# ProProject_PetCareSTM32_MiniSTM32_2024-0.net
KiCad netlist of a schematic drawn in EasyEDA Pro
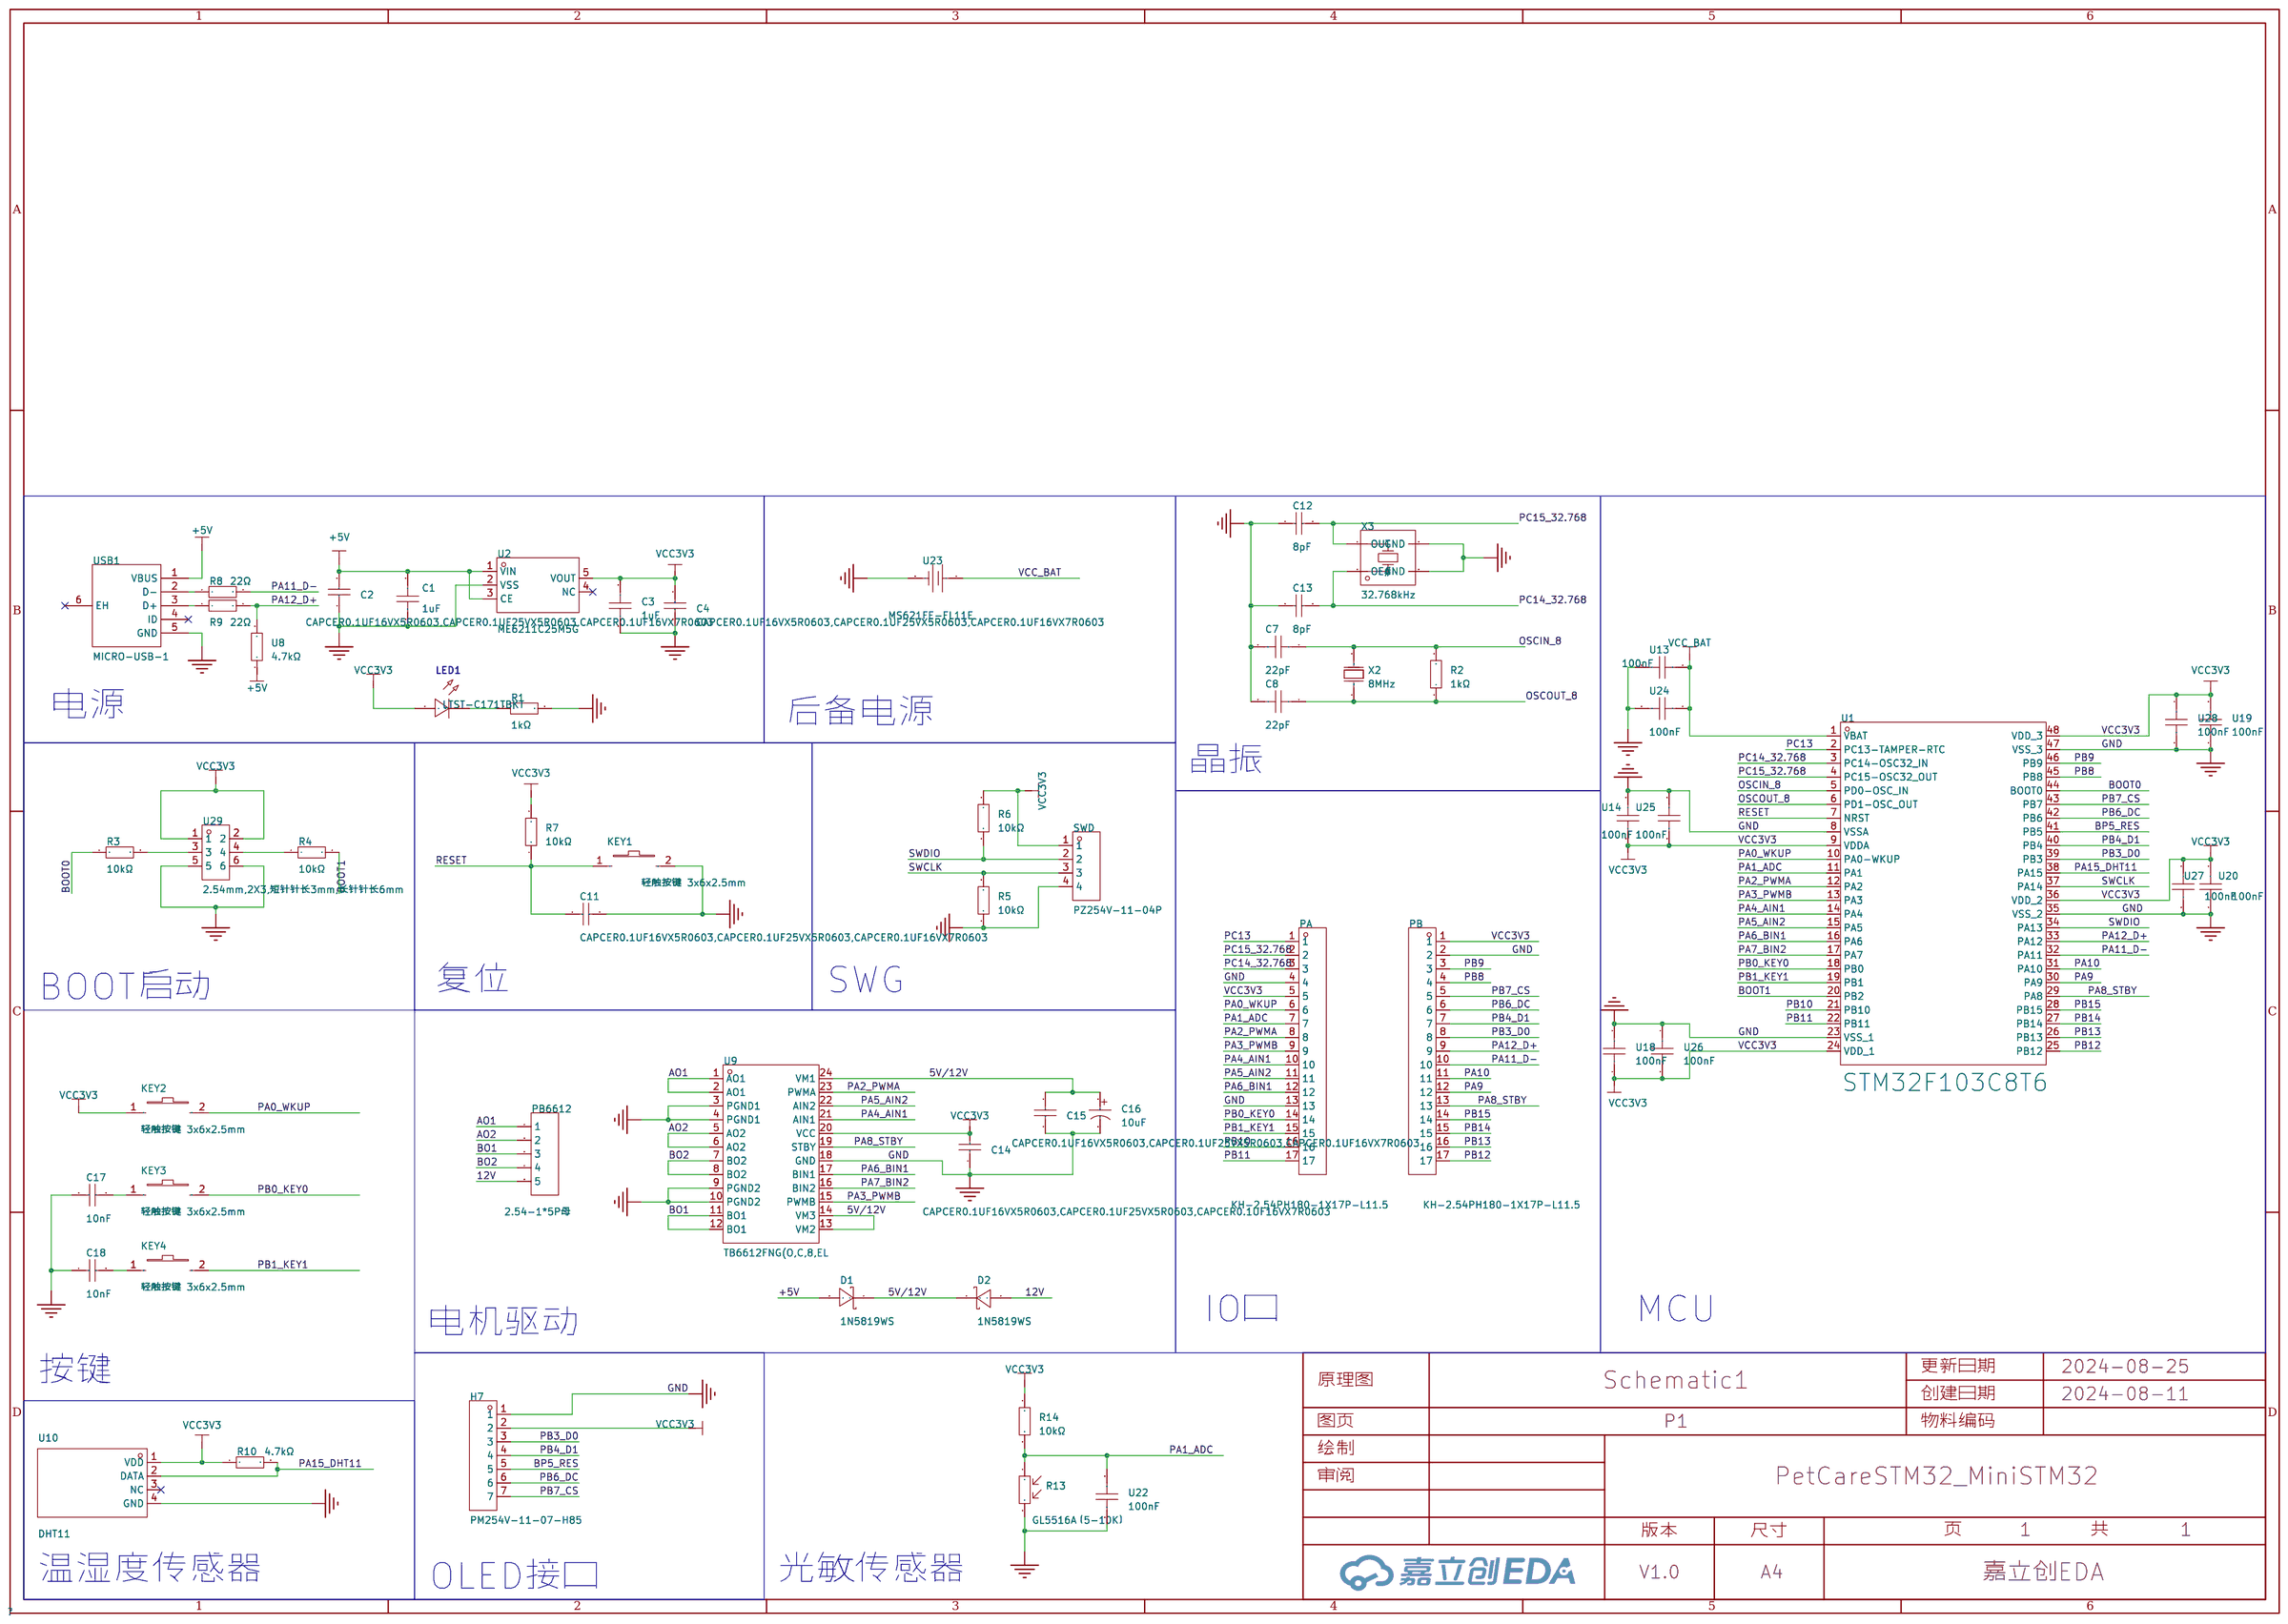
[diagram p0: schematic sheet]

(export (version "E")
  (design (tool "Eeschema 10.0.6"))
  (components
    (comp (ref "C1")
      (value "1uF")
      (footprint "easyedapro:C0603")
      (description "容值:1uF;精度:±10%;额定电压:50V;材质(温度系数):X5R;")
      (fields
        (field (name "Manufacturer Part") "CL10A105KB8NNNC")
        (field (name "Manufacturer") "SAMSUNG(三星)")
      )
      (libsource (lib "easyedapro") (part "CL10A105KB8NNNC"))
    )
    (comp (ref "C2")
      (value "CAPCER0.1UF16VX5R0603,CAPCER0.1UF25VX5R0603,CAPCER0.1UF16VX7R0603")
      (footprint "easyedapro:C0603")
      (libsource (lib "easyedapro") (part "CAPCER0.1UF16VX5R0603,CAPCER0.1UF25VX5R0603,CAPCER0.1UF16VX7R0603"))
    )
    (comp (ref "C3")
      (value "1uF")
      (footprint "easyedapro:C0603")
      (description "容值:1uF;精度:±10%;额定电压:50V;材质(温度系数):X5R;")
      (fields
        (field (name "Manufacturer Part") "CL10A105KB8NNNC")
        (field (name "Manufacturer") "SAMSUNG(三星)")
      )
      (libsource (lib "easyedapro") (part "CL10A105KB8NNNC"))
    )
    (comp (ref "C4")
      (value "CAPCER0.1UF16VX5R0603,CAPCER0.1UF25VX5R0603,CAPCER0.1UF16VX7R0603")
      (footprint "easyedapro:C0603")
      (libsource (lib "easyedapro") (part "CAPCER0.1UF16VX5R0603,CAPCER0.1UF25VX5R0603,CAPCER0.1UF16VX7R0603"))
    )
    (comp (ref "C7")
      (value "22pF")
      (footprint "easyedapro:C0603")
      (description "容值:22pF;精度:±5%;额定电压:50V;材质(温度系数):C0G;")
      (fields
        (field (name "Manufacturer Part") "CL10C220JB81PNC")
        (field (name "Manufacturer") "SAMSUNG(三星)")
      )
      (libsource (lib "easyedapro") (part "CL10C220JB81PNC"))
    )
    (comp (ref "C8")
      (value "22pF")
      (footprint "easyedapro:C0603")
      (description "容值:22pF;精度:±5%;额定电压:50V;材质(温度系数):C0G;")
      (fields
        (field (name "Manufacturer Part") "CL10C220JB81PNC")
        (field (name "Manufacturer") "SAMSUNG(三星)")
      )
      (libsource (lib "easyedapro") (part "CL10C220JB81PNC"))
    )
    (comp (ref "C11")
      (value "CAPCER0.1UF16VX5R0603,CAPCER0.1UF25VX5R0603,CAPCER0.1UF16VX7R0603")
      (footprint "easyedapro:C0603")
      (libsource (lib "easyedapro") (part "CAPCER0.1UF16VX5R0603,CAPCER0.1UF25VX5R0603,CAPCER0.1UF16VX7R0603"))
    )
    (comp (ref "C12")
      (value "8pF")
      (footprint "easyedapro:C0603")
      (description "容值:8pF;额定电压:50V;材质(温度系数):C0G;")
      (fields (field (name "Manufacturer Part") "0603CG8R0C500NT") (field (name "Manufacturer") "FH(风华)"))
      (libsource (lib "easyedapro") (part "0603CG8R0C500NT_C36508"))
    )
    (comp (ref "C13")
      (value "8pF")
      (footprint "easyedapro:C0603")
      (description "容值:8pF;额定电压:50V;材质(温度系数):C0G;")
      (fields (field (name "Manufacturer Part") "0603CG8R0C500NT") (field (name "Manufacturer") "FH(风华)"))
      (libsource (lib "easyedapro") (part "0603CG8R0C500NT_C36508"))
    )
    (comp (ref "C14")
      (value "CAPCER0.1UF16VX5R0603,CAPCER0.1UF25VX5R0603,CAPCER0.1UF16VX7R0603")
      (footprint "easyedapro:C0603")
      (libsource (lib "easyedapro") (part "CAPCER0.1UF16VX5R0603,CAPCER0.1UF25VX5R0603,CAPCER0.1UF16VX7R0603"))
    )
    (comp (ref "C15")
      (value "CAPCER0.1UF16VX5R0603,CAPCER0.1UF25VX5R0603,CAPCER0.1UF16VX7R0603")
      (footprint "easyedapro:C0603")
      (libsource (lib "easyedapro") (part "CAPCER0.1UF16VX5R0603,CAPCER0.1UF25VX5R0603,CAPCER0.1UF16VX7R0603"))
    )
    (comp (ref "C16")
      (value "10uF")
      (footprint "easyedapro:CAP-TH_BD5.0-P2.00-D0.8-FD")
      (description "容值:10uF;精度:±20%;额定电压:25V;")
      (fields (field (name "Manufacturer Part") "KF100M025C110A") (field (name "Manufacturer") "CapXon(丰宾)"))
      (libsource (lib "easyedapro") (part "KF100M025C110A"))
    )
    (comp (ref "C17")
      (value "10nF")
      (footprint "easyedapro:C0603")
      (description "容值:10nF;精度:±10%;额定电压:50V;材质(温度系数):X7R;")
      (fields
        (field (name "Manufacturer Part") "CC0603KRX7R9BB103")
        (field (name "Manufacturer") "YAGEO(国巨)")
      )
      (libsource (lib "easyedapro") (part "CC0603KRX7R9BB103"))
    )
    (comp (ref "C18")
      (value "10nF")
      (footprint "easyedapro:C0603")
      (description "容值:10nF;精度:±10%;额定电压:50V;材质(温度系数):X7R;")
      (fields
        (field (name "Manufacturer Part") "CC0603KRX7R9BB103")
        (field (name "Manufacturer") "YAGEO(国巨)")
      )
      (libsource (lib "easyedapro") (part "CC0603KRX7R9BB103"))
    )
    (comp (ref "D1")
      (value "1N5819WS")
      (footprint "easyedapro:SOD-323_L1.8-W1.3-LS2.5-RD")
      (description "正向压降(Vf):600mV@1A;直流反向耐压(Vr):40V;平均整流电流(Io):1A;")
      (fields (field (name "Manufacturer") "Hottech(合科泰)"))
      (libsource (lib "easyedapro") (part "1N5819WS"))
    )
    (comp (ref "D2")
      (value "1N5819WS")
      (footprint "easyedapro:SOD-323_L1.8-W1.3-LS2.5-RD")
      (description "正向压降(Vf):600mV@1A;直流反向耐压(Vr):40V;平均整流电流(Io):1A;")
      (fields (field (name "Manufacturer") "Hottech(合科泰)"))
      (libsource (lib "easyedapro") (part "1N5819WS"))
    )
    (comp (ref "H7")
      (value "PM254V-11-07-H85")
      (footprint "easyedapro:HDR-TH_7P-P2.54-V-F")
      (fields (field (name "Manufacturer") "XFCN(兴飞)"))
      (libsource (lib "easyedapro") (part "PM254V-11-07-H85"))
    )
    (comp (ref "KEY1")
      (value "轻触按键 3x6x2.5mm")
      (footprint "easyedapro:SW-SMD_L6.0-W3.6-LS8.0")
      (libsource (lib "easyedapro") (part "3x6x2.5mm"))
    )
    (comp (ref "KEY2")
      (value "轻触按键 3x6x2.5mm")
      (footprint "easyedapro:SW-SMD_L6.0-W3.6-LS8.0")
      (libsource (lib "easyedapro") (part "3x6x2.5mm"))
    )
    (comp (ref "KEY3")
      (value "轻触按键 3x6x2.5mm")
      (footprint "easyedapro:SW-SMD_L6.0-W3.6-LS8.0")
      (libsource (lib "easyedapro") (part "3x6x2.5mm"))
    )
    (comp (ref "KEY4")
      (value "轻触按键 3x6x2.5mm")
      (footprint "easyedapro:SW-SMD_L6.0-W3.6-LS8.0")
      (libsource (lib "easyedapro") (part "3x6x2.5mm"))
    )
    (comp (ref "LED1")
      (value "LTST-C171TBKT")
      (footprint "easyedapro:LED_0805")
      (fields (field (name "Manufacturer") "LITEON(光宝)"))
      (libsource (lib "easyedapro") (part "LED_B"))
    )
    (comp (ref "PA")
      (value "KH-2.54PH180-1X17P-L11.5")
      (footprint "easyedapro:HDR-TH_17P-P2.54-V-M")
      (fields (field (name "Manufacturer") "kinghelm(金航标)"))
      (libsource (lib "easyedapro") (part "KH-2.54PH180-1X17P-L11.5"))
    )
    (comp (ref "PB")
      (value "KH-2.54PH180-1X17P-L11.5")
      (footprint "easyedapro:HDR-TH_17P-P2.54-V-M")
      (fields (field (name "Manufacturer") "kinghelm(金航标)"))
      (libsource (lib "easyedapro") (part "KH-2.54PH180-1X17P-L11.5"))
    )
    (comp (ref "PB6612")
      (value "2.54-1*5P母")
      (footprint "easyedapro:HDR-TH_5P-P2.54-V-F")
      (description "插孔结构:1x5P;间距:2.54mm;行距:-;安装类型:直插;排数:单排;总孔位数:5P;塑高:-;触头材质:-;触头镀层:-;")
      (fields (field (name "Manufacturer") "BOOMELE(博穆精密)"))
      (libsource (lib "easyedapro") (part "Header-Female-2.54_1x5"))
    )
    (comp (ref "R1")
      (value "1kΩ")
      (footprint "easyedapro:R0603")
      (description "电阻类型:厚膜电阻;阻值:1kΩ;精度:±1%;功率:100mW;最大工作电压:75V;温度系数:±100ppm/°C;")
      (fields (field (name "Manufacturer Part") "RC0603FR-071KL") (field (name "Manufacturer") "YAGEO(国巨)"))
      (libsource (lib "easyedapro") (part "RC0603FR-071KL"))
    )
    (comp (ref "R2")
      (value "1kΩ")
      (footprint "easyedapro:R0603")
      (description "电阻类型:厚膜电阻;阻值:1kΩ;精度:±0.5%;功率:100mW;最大工作电压:75V;温度系数:±100ppm/°C;")
      (fields
        (field (name "Manufacturer Part") "0603WAD1001T5E")
        (field (name "Manufacturer") "UNI-ROYAL(厚声)")
      )
      (libsource (lib "easyedapro") (part "0603WAD1001T5E"))
    )
    (comp (ref "R3")
      (value "10kΩ")
      (footprint "easyedapro:R0603")
      (description "电阻类型:厚膜电阻;阻值:10kΩ;精度:±1%;功率:100mW;最大工作电压:75V;温度系数:±100ppm/°C;")
      (fields
        (field (name "Manufacturer Part") "0603WAF1002T5E")
        (field (name "Manufacturer") "UNI-ROYAL(厚声)")
      )
      (libsource (lib "easyedapro") (part "0603WAF1002T5E"))
    )
    (comp (ref "R4")
      (value "10kΩ")
      (footprint "easyedapro:R0603")
      (description "电阻类型:厚膜电阻;阻值:10kΩ;精度:±1%;功率:100mW;最大工作电压:75V;温度系数:±100ppm/°C;")
      (fields
        (field (name "Manufacturer Part") "0603WAF1002T5E")
        (field (name "Manufacturer") "UNI-ROYAL(厚声)")
      )
      (libsource (lib "easyedapro") (part "0603WAF1002T5E"))
    )
    (comp (ref "R5")
      (value "10kΩ")
      (footprint "easyedapro:R0603")
      (description "电阻类型:厚膜电阻;阻值:10kΩ;精度:±1%;功率:100mW;最大工作电压:75V;温度系数:±100ppm/°C;")
      (fields
        (field (name "Manufacturer Part") "0603WAF1002T5E")
        (field (name "Manufacturer") "UNI-ROYAL(厚声)")
      )
      (libsource (lib "easyedapro") (part "0603WAF1002T5E"))
    )
    (comp (ref "R6")
      (value "10kΩ")
      (footprint "easyedapro:R0603")
      (description "电阻类型:厚膜电阻;阻值:10kΩ;精度:±1%;功率:100mW;最大工作电压:75V;温度系数:±100ppm/°C;")
      (fields
        (field (name "Manufacturer Part") "0603WAF1002T5E")
        (field (name "Manufacturer") "UNI-ROYAL(厚声)")
      )
      (libsource (lib "easyedapro") (part "0603WAF1002T5E"))
    )
    (comp (ref "R7")
      (value "10kΩ")
      (footprint "easyedapro:R0603")
      (description "电阻类型:厚膜电阻;阻值:10kΩ;精度:±1%;功率:100mW;最大工作电压:75V;温度系数:±100ppm/°C;")
      (fields
        (field (name "Manufacturer Part") "0603WAF1002T5E")
        (field (name "Manufacturer") "UNI-ROYAL(厚声)")
      )
      (libsource (lib "easyedapro") (part "0603WAF1002T5E"))
    )
    (comp (ref "R8")
      (value "22Ω")
      (footprint "easyedapro:R0805")
      (description "电阻类型:薄膜电阻;阻值:22Ω;精度:±1%;功率:250mW;最大工作电压:150V;温度系数:±25ppm/°C;")
      (fields
        (field (name "Manufacturer Part") "TC0525F220JT5E")
        (field (name "Manufacturer") "UNI-ROYAL(厚声)")
      )
      (libsource (lib "easyedapro") (part "TC0525F220JT5E"))
    )
    (comp (ref "R9")
      (value "22Ω")
      (footprint "easyedapro:R0805")
      (description "电阻类型:薄膜电阻;阻值:22Ω;精度:±1%;功率:250mW;最大工作电压:150V;温度系数:±25ppm/°C;")
      (fields
        (field (name "Manufacturer Part") "TC0525F220JT5E")
        (field (name "Manufacturer") "UNI-ROYAL(厚声)")
      )
      (libsource (lib "easyedapro") (part "TC0525F220JT5E"))
    )
    (comp (ref "R10")
      (value "4.7kΩ")
      (footprint "easyedapro:R1206")
      (description "电阻类型:厚膜电阻;阻值:4.7kΩ;精度:±1%;功率:250mW;最大工作电压:200V;温度系数:±100ppm/°C;")
      (fields
        (field (name "Manufacturer Part") "1206W4F4701T5E")
        (field (name "Manufacturer") "UNI-ROYAL(厚声)")
      )
      (libsource (lib "easyedapro") (part "1206W4F4701T5E"))
    )
    (comp (ref "R13")
      (value "GL5516A（5-10K）")
      (footprint "easyedapro:RES-TH_L5.1-W4.3-P3.40_GL55")
      (description "暗电阻:200kΩ;亮电阻 @ 10Lux:5kΩ~10kΩ;光谱峰值(波长):540nm;")
      (fields (field (name "Manufacturer") "JCHL(晶创和立)"))
      (libsource (lib "easyedapro") (part "GL5516A(5-10K)"))
    )
    (comp (ref "R14")
      (value "10kΩ")
      (footprint "easyedapro:R0603")
      (description "电阻类型:厚膜电阻;阻值:10kΩ;精度:±1%;功率:100mW;最大工作电压:75V;温度系数:±100ppm/°C;")
      (fields
        (field (name "Manufacturer Part") "0603WAF1002T5E")
        (field (name "Manufacturer") "UNI-ROYAL(厚声)")
      )
      (libsource (lib "easyedapro") (part "0603WAF1002T5E"))
    )
    (comp (ref "SWD")
      (value "PZ254V-11-04P")
      (footprint "easyedapro:HDR-TH_4P-P2.54-V-M")
      (fields (field (name "Manufacturer") "XFCN(兴飞)"))
      (libsource (lib "easyedapro") (part "PZ254V-11-04P_C2691448"))
    )
    (comp (ref "U1")
      (value "STM32F103C8T6")
      (footprint "easyedapro:LQFP-48_L7.0-W7.0-P0.50-LS9.0-BL")
      (description "CPU内核:ARM-M3;程序存储容量:64KB;RAM总容量:20KB;GPIO端口数量:37;工作电压范围:2V~3.6V;CPU最大主频:72MHz;程序存储器类型:FLASH;")
      (fields (field (name "Manufacturer") "ST(意法半导体)"))
      (libsource (lib "easyedapro") (part "STM32F103C8T6"))
    )
    (comp (ref "U2")
      (value "ME6211C25M5G")
      (footprint "easyedapro:SOT-23-5_L2.9-W1.7-P0.95-LS2.8-BL")
      (fields (field (name "Manufacturer") "MICRONE(南京微盟)"))
      (libsource (lib "easyedapro") (part "ME6211C25M5G"))
    )
    (comp (ref "U8")
      (value "4.7kΩ")
      (footprint "easyedapro:R0603")
      (description "电阻类型:薄膜电阻;阻值:4.7kΩ;精度:±1%;功率:100mW;最大工作电压:75V;温度系数:±50ppm/°C;")
      (fields (field (name "Manufacturer Part") "AR03FTDX4701A") (field (name "Manufacturer") "Viking(光颉)"))
      (libsource (lib "easyedapro") (part "AR03FTDX4701A"))
    )
    (comp (ref "U9")
      (value "TB6612FNG(O,C,8,EL")
      (footprint "easyedapro:SSOP-24_L8.4-W5.8-P0.65-LS7.8-BL")
      (description "双直流电机驱动器集成电路")
      (fields (field (name "Manufacturer") "TOSHIBA(东芝)"))
      (libsource (lib "easyedapro") (part "TB6612FNG(O,C,8,EL"))
    )
    (comp (ref "U10")
      (value "DHT11")
      (footprint "easyedapro:SENSOR-TH_DHT11")
      (description "新款电容式数字温湿度传感器,老款已停产16.1x12.6x5.8mm")
      (fields (field (name "Manufacturer") "广州奥松"))
      (libsource (lib "easyedapro") (part "DHT11"))
    )
    (comp (ref "U13")
      (value "100nF")
      (footprint "easyedapro:C0603")
      (description "容值:100nF;精度:±10%;额定电压:50V;材质(温度系数):X7R;")
      (fields
        (field (name "Manufacturer Part") "CGA0603X7R104K500JT")
        (field (name "Manufacturer") "HRE(芯声)")
      )
      (libsource (lib "easyedapro") (part "CGA0603X7R104K500JT"))
    )
    (comp (ref "U14")
      (value "100nF")
      (footprint "easyedapro:C0603")
      (description "容值:100nF;精度:±10%;额定电压:50V;材质(温度系数):X7R;")
      (fields
        (field (name "Manufacturer Part") "CGA0603X7R104K500JT")
        (field (name "Manufacturer") "HRE(芯声)")
      )
      (libsource (lib "easyedapro") (part "CGA0603X7R104K500JT"))
    )
    (comp (ref "U18")
      (value "100nF")
      (footprint "easyedapro:C0603")
      (description "容值:100nF;精度:±10%;额定电压:50V;材质(温度系数):X7R;")
      (fields
        (field (name "Manufacturer Part") "CGA0603X7R104K500JT")
        (field (name "Manufacturer") "HRE(芯声)")
      )
      (libsource (lib "easyedapro") (part "CGA0603X7R104K500JT"))
    )
    (comp (ref "U19")
      (value "100nF")
      (footprint "easyedapro:C0603")
      (description "容值:100nF;精度:±10%;额定电压:50V;材质(温度系数):X7R;")
      (fields
        (field (name "Manufacturer Part") "CGA0603X7R104K500JT")
        (field (name "Manufacturer") "HRE(芯声)")
      )
      (libsource (lib "easyedapro") (part "CGA0603X7R104K500JT"))
    )
    (comp (ref "U20")
      (value "100nF")
      (footprint "easyedapro:C0603")
      (description "容值:100nF;精度:±10%;额定电压:50V;材质(温度系数):X7R;")
      (fields
        (field (name "Manufacturer Part") "CGA0603X7R104K500JT")
        (field (name "Manufacturer") "HRE(芯声)")
      )
      (libsource (lib "easyedapro") (part "CGA0603X7R104K500JT"))
    )
    (comp (ref "U22")
      (value "100nF")
      (footprint "easyedapro:C0603")
      (description "容值:100nF;精度:±10%;额定电压:50V;材质(温度系数):X7R;")
      (fields
        (field (name "Manufacturer Part") "CGA0603X7R104K500JT")
        (field (name "Manufacturer") "HRE(芯声)")
      )
      (libsource (lib "easyedapro") (part "CGA0603X7R104K500JT"))
    )
    (comp (ref "U23")
      (value "MS621FE-FL11E")
      (footprint "easyedapro:BAT-SMD_FL11E")
      (description "FL11E 3.3V可充电纽扣电池 5.5mAH")
      (fields (field (name "Manufacturer") "Seiko(精工)"))
      (libsource (lib "easyedapro") (part "MS621FE-FL11E"))
    )
    (comp (ref "U24")
      (value "100nF")
      (footprint "easyedapro:C0603")
      (description "容值:100nF;精度:±10%;额定电压:50V;材质(温度系数):X7R;")
      (fields
        (field (name "Manufacturer Part") "CGA0603X7R104K500JT")
        (field (name "Manufacturer") "HRE(芯声)")
      )
      (libsource (lib "easyedapro") (part "CGA0603X7R104K500JT"))
    )
    (comp (ref "U25")
      (value "100nF")
      (footprint "easyedapro:C0603")
      (description "容值:100nF;精度:±10%;额定电压:50V;材质(温度系数):X7R;")
      (fields
        (field (name "Manufacturer Part") "CGA0603X7R104K500JT")
        (field (name "Manufacturer") "HRE(芯声)")
      )
      (libsource (lib "easyedapro") (part "CGA0603X7R104K500JT"))
    )
    (comp (ref "U26")
      (value "100nF")
      (footprint "easyedapro:C0603")
      (description "容值:100nF;精度:±10%;额定电压:50V;材质(温度系数):X7R;")
      (fields
        (field (name "Manufacturer Part") "CGA0603X7R104K500JT")
        (field (name "Manufacturer") "HRE(芯声)")
      )
      (libsource (lib "easyedapro") (part "CGA0603X7R104K500JT"))
    )
    (comp (ref "U27")
      (value "100nF")
      (footprint "easyedapro:C0603")
      (description "容值:100nF;精度:±10%;额定电压:50V;材质(温度系数):X7R;")
      (fields
        (field (name "Manufacturer Part") "CGA0603X7R104K500JT")
        (field (name "Manufacturer") "HRE(芯声)")
      )
      (libsource (lib "easyedapro") (part "CGA0603X7R104K500JT"))
    )
    (comp (ref "U28")
      (value "100nF")
      (footprint "easyedapro:C0603")
      (description "容值:100nF;精度:±10%;额定电压:50V;材质(温度系数):X7R;")
      (fields
        (field (name "Manufacturer Part") "CGA0603X7R104K500JT")
        (field (name "Manufacturer") "HRE(芯声)")
      )
      (libsource (lib "easyedapro") (part "CGA0603X7R104K500JT"))
    )
    (comp (ref "U29")
      (value "2.54mm,2X3,短针针长3mm,长针针长6mm")
      (footprint "easyedapro:HDR-TH_6P-P2.54-V-M-R2-C3-S2.54-2")
      (libsource (lib "easyedapro") (part "2.54MM,2X3,短针针长3MM,长针针长6MM"))
    )
    (comp (ref "USB1")
      (value "MICRO-USB-1")
      (footprint "easyedapro:MICRO-USB-SMD_C9900008946")
      (libsource (lib "easyedapro") (part "MICRO-USB-1"))
    )
    (comp (ref "X2")
      (value "8MHz")
      (footprint "easyedapro:OSC-SMD_L5.0-W3.2")
      (description "晶振类型:贴片晶振;频率:8MHz;常温频差:±20ppm;外接负载电容:18pF;频率稳定度(全温):±30ppm;")
      (fields
        (field (name "Manufacturer Part") "ABM3-8.000MHZ-D2Y-T")
        (field (name "Manufacturer") "ABRACON")
      )
      (libsource (lib "easyedapro") (part "ABM3-8.000MHZ-D2Y-T"))
    )
    (comp (ref "X3")
      (value "32.768kHz")
      (footprint "easyedapro:CRYSTAL-SMD_4P-L8.0-W3.8-BL")
      (description "晶振类型:-;频率:32.768kHz;常温频差:±20ppm;外接负载电容:12.5pF;频率稳定度(全温):-;")
      (fields (field (name "Manufacturer Part") "ABS25-32.768KHZ-T") (field (name "Manufacturer") "ABRACON"))
      (libsource (lib "easyedapro") (part "ABS25-32.768KHZ-T"))
    )
  )
  (nets
    (net (code "1") (name "+5V") (class "Default")
      (node (ref "C1") (pin "2") (pinfunction "2_2") (pintype "unspecified"))
      (node (ref "C2") (pin "2") (pinfunction "2_2") (pintype "input"))
      (node (ref "D1") (pin "2") (pinfunction "A_2") (pintype "unspecified"))
      (node (ref "U2") (pin "1") (pinfunction "VIN_1") (pintype "unspecified"))
      (node (ref "U2") (pin "3") (pinfunction "CE_3") (pintype "unspecified"))
      (node (ref "U8") (pin "1") (pinfunction "1_1") (pintype "unspecified"))
      (node (ref "USB1") (pin "1") (pinfunction "VBUS_1") (pintype "input"))
    )
    (net (code "2") (name "/5V{slash}12V") (class "Default")
      (node (ref "C15") (pin "2") (pinfunction "2_2") (pintype "input"))
      (node (ref "C16") (pin "1") (pinfunction "1_1") (pintype "input"))
      (node (ref "D1") (pin "1") (pinfunction "K_1") (pintype "unspecified"))
      (node (ref "D2") (pin "1") (pinfunction "K_1") (pintype "unspecified"))
      (node (ref "U9") (pin "13") (pinfunction "VM2_13") (pintype "unspecified"))
      (node (ref "U9") (pin "14") (pinfunction "VM3_14") (pintype "unspecified"))
      (node (ref "U9") (pin "24") (pinfunction "VM1_24") (pintype "unspecified"))
    )
    (net (code "3") (name "/12V") (class "Default")
      (node (ref "D2") (pin "2") (pinfunction "A_2") (pintype "unspecified"))
      (node (ref "PB6612") (pin "5") (pinfunction "5_5") (pintype "input"))
    )
    (net (code "4") (name "/AO1") (class "Default")
      (node (ref "PB6612") (pin "1") (pinfunction "1_1") (pintype "input"))
      (node (ref "U9") (pin "1") (pinfunction "AO1_1") (pintype "unspecified"))
      (node (ref "U9") (pin "2") (pinfunction "AO1_2") (pintype "unspecified"))
    )
    (net (code "5") (name "/AO2") (class "Default")
      (node (ref "PB6612") (pin "2") (pinfunction "2_2") (pintype "input"))
      (node (ref "U9") (pin "5") (pinfunction "AO2_5") (pintype "unspecified"))
      (node (ref "U9") (pin "6") (pinfunction "AO2_6") (pintype "unspecified"))
    )
    (net (code "6") (name "/BO1") (class "Default")
      (node (ref "PB6612") (pin "3") (pinfunction "3_3") (pintype "input"))
      (node (ref "U9") (pin "11") (pinfunction "BO1_11") (pintype "unspecified"))
      (node (ref "U9") (pin "12") (pinfunction "BO1_12") (pintype "unspecified"))
    )
    (net (code "7") (name "/BO2") (class "Default")
      (node (ref "PB6612") (pin "4") (pinfunction "4_4") (pintype "input"))
      (node (ref "U9") (pin "7") (pinfunction "BO2_7") (pintype "unspecified"))
      (node (ref "U9") (pin "8") (pinfunction "BO2_8") (pintype "unspecified"))
    )
    (net (code "8") (name "/BOOT0") (class "Default")
      (node (ref "R3") (pin "1") (pinfunction "1_1") (pintype "input"))
      (node (ref "U1") (pin "44") (pinfunction "BOOT0_44") (pintype "unspecified"))
    )
    (net (code "9") (name "/BOOT1") (class "Default")
      (node (ref "R4") (pin "2") (pinfunction "2_2") (pintype "input"))
      (node (ref "U1") (pin "20") (pinfunction "PB2_20") (pintype "unspecified"))
    )
    (net (code "10") (name "/BP5_RES") (class "Default")
      (node (ref "H7") (pin "5") (pinfunction "5_5") (pintype "unspecified"))
      (node (ref "U1") (pin "41") (pinfunction "PB5_41") (pintype "unspecified"))
    )
    (net (code "11") (name "/OSCIN_8") (class "Default")
      (node (ref "C7") (pin "1") (pinfunction "1_1") (pintype "unspecified"))
      (node (ref "R2") (pin "2") (pinfunction "2_2") (pintype "input"))
      (node (ref "U1") (pin "5") (pinfunction "PD0-OSC_IN_5") (pintype "unspecified"))
      (node (ref "X2") (pin "2") (pinfunction "OSC2_2") (pintype "input"))
    )
    (net (code "12") (name "/OSCOUT_8") (class "Default")
      (node (ref "C8") (pin "1") (pinfunction "1_1") (pintype "unspecified"))
      (node (ref "R2") (pin "1") (pinfunction "1_1") (pintype "input"))
      (node (ref "U1") (pin "6") (pinfunction "PD1-OSC_OUT_6") (pintype "unspecified"))
      (node (ref "X2") (pin "1") (pinfunction "OSC1_1") (pintype "input"))
    )
    (net (code "13") (name "/PA0_WKUP") (class "Default")
      (node (ref "KEY2") (pin "2") (pinfunction "2_2") (pintype "input"))
      (node (ref "PA") (pin "6") (pinfunction "6_6") (pintype "unspecified"))
      (node (ref "U1") (pin "10") (pinfunction "PA0-WKUP_10") (pintype "unspecified"))
    )
    (net (code "14") (name "/PA1_ADC") (class "Default")
      (node (ref "PA") (pin "7") (pinfunction "7_7") (pintype "unspecified"))
      (node (ref "R13") (pin "1") (pinfunction "1_1") (pintype "input"))
      (node (ref "R14") (pin "1") (pinfunction "1_1") (pintype "input"))
      (node (ref "U1") (pin "11") (pinfunction "PA1_11") (pintype "unspecified"))
      (node (ref "U22") (pin "2") (pinfunction "2_2") (pintype "unspecified"))
    )
    (net (code "15") (name "/PA2_PWMA") (class "Default")
      (node (ref "PA") (pin "8") (pinfunction "8_8") (pintype "unspecified"))
      (node (ref "U1") (pin "12") (pinfunction "PA2_12") (pintype "unspecified"))
      (node (ref "U9") (pin "23") (pinfunction "PWMA_23") (pintype "unspecified"))
    )
    (net (code "16") (name "/PA3_PWMB") (class "Default")
      (node (ref "PA") (pin "9") (pinfunction "9_9") (pintype "unspecified"))
      (node (ref "U1") (pin "13") (pinfunction "PA3_13") (pintype "unspecified"))
      (node (ref "U9") (pin "15") (pinfunction "PWMB_15") (pintype "unspecified"))
    )
    (net (code "17") (name "/PA4_AIN1") (class "Default")
      (node (ref "PA") (pin "10") (pinfunction "10_10") (pintype "unspecified"))
      (node (ref "U1") (pin "14") (pinfunction "PA4_14") (pintype "unspecified"))
      (node (ref "U9") (pin "21") (pinfunction "AIN1_21") (pintype "unspecified"))
    )
    (net (code "18") (name "/PA5_AIN2") (class "Default")
      (node (ref "PA") (pin "11") (pinfunction "11_11") (pintype "unspecified"))
      (node (ref "U1") (pin "15") (pinfunction "PA5_15") (pintype "unspecified"))
      (node (ref "U9") (pin "22") (pinfunction "AIN2_22") (pintype "unspecified"))
    )
    (net (code "19") (name "/PA6_BIN1") (class "Default")
      (node (ref "PA") (pin "12") (pinfunction "12_12") (pintype "unspecified"))
      (node (ref "U1") (pin "16") (pinfunction "PA6_16") (pintype "unspecified"))
      (node (ref "U9") (pin "17") (pinfunction "BIN1_17") (pintype "unspecified"))
    )
    (net (code "20") (name "/PA7_BIN2") (class "Default")
      (node (ref "U1") (pin "17") (pinfunction "PA7_17") (pintype "unspecified"))
      (node (ref "U9") (pin "16") (pinfunction "BIN2_16") (pintype "unspecified"))
    )
    (net (code "21") (name "/PA8_STBY") (class "Default")
      (node (ref "PB") (pin "13") (pinfunction "13_13") (pintype "unspecified"))
      (node (ref "U1") (pin "29") (pinfunction "PA8_29") (pintype "unspecified"))
      (node (ref "U9") (pin "19") (pinfunction "STBY_19") (pintype "unspecified"))
    )
    (net (code "22") (name "/PA9") (class "Default")
      (node (ref "PB") (pin "12") (pinfunction "12_12") (pintype "unspecified"))
      (node (ref "U1") (pin "30") (pinfunction "PA9_30") (pintype "unspecified"))
    )
    (net (code "23") (name "/PA10") (class "Default")
      (node (ref "PB") (pin "11") (pinfunction "11_11") (pintype "unspecified"))
      (node (ref "U1") (pin "31") (pinfunction "PA10_31") (pintype "unspecified"))
    )
    (net (code "24") (name "/PA11_D-") (class "Default")
      (node (ref "PB") (pin "10") (pinfunction "10_10") (pintype "unspecified"))
      (node (ref "R8") (pin "2") (pinfunction "2_2") (pintype "input"))
      (node (ref "U1") (pin "32") (pinfunction "PA11_32") (pintype "unspecified"))
    )
    (net (code "25") (name "/PA12_D+") (class "Default")
      (node (ref "PB") (pin "9") (pinfunction "9_9") (pintype "unspecified"))
      (node (ref "R9") (pin "2") (pinfunction "2_2") (pintype "input"))
      (node (ref "U1") (pin "33") (pinfunction "PA12_33") (pintype "unspecified"))
      (node (ref "U8") (pin "2") (pinfunction "2_2") (pintype "unspecified"))
    )
    (net (code "26") (name "/PA15_DHT11") (class "Default")
      (node (ref "R10") (pin "2") (pinfunction "2_2") (pintype "input"))
      (node (ref "U1") (pin "38") (pinfunction "PA15_38") (pintype "unspecified"))
      (node (ref "U10") (pin "2") (pinfunction "DATA_2") (pintype "unspecified"))
    )
    (net (code "27") (name "/PB0_KEY0") (class "Default")
      (node (ref "KEY3") (pin "2") (pinfunction "2_2") (pintype "input"))
      (node (ref "PA") (pin "14") (pinfunction "14_14") (pintype "unspecified"))
      (node (ref "U1") (pin "18") (pinfunction "PB0_18") (pintype "unspecified"))
    )
    (net (code "28") (name "/PB1_KEY1") (class "Default")
      (node (ref "KEY4") (pin "2") (pinfunction "2_2") (pintype "input"))
      (node (ref "PA") (pin "15") (pinfunction "15_15") (pintype "unspecified"))
      (node (ref "U1") (pin "19") (pinfunction "PB1_19") (pintype "unspecified"))
    )
    (net (code "29") (name "/PB3_D0") (class "Default")
      (node (ref "H7") (pin "3") (pinfunction "3_3") (pintype "unspecified"))
      (node (ref "PB") (pin "8") (pinfunction "8_8") (pintype "unspecified"))
      (node (ref "U1") (pin "39") (pinfunction "PB3_39") (pintype "unspecified"))
    )
    (net (code "30") (name "/PB4_D1") (class "Default")
      (node (ref "H7") (pin "4") (pinfunction "4_4") (pintype "unspecified"))
      (node (ref "PB") (pin "7") (pinfunction "7_7") (pintype "unspecified"))
      (node (ref "U1") (pin "40") (pinfunction "PB4_40") (pintype "unspecified"))
    )
    (net (code "31") (name "/PB6_DC") (class "Default")
      (node (ref "H7") (pin "6") (pinfunction "6_6") (pintype "unspecified"))
      (node (ref "PB") (pin "6") (pinfunction "6_6") (pintype "unspecified"))
      (node (ref "U1") (pin "42") (pinfunction "PB6_42") (pintype "unspecified"))
    )
    (net (code "32") (name "/PB7_CS") (class "Default")
      (node (ref "H7") (pin "7") (pinfunction "7_7") (pintype "unspecified"))
      (node (ref "PB") (pin "5") (pinfunction "5_5") (pintype "unspecified"))
      (node (ref "U1") (pin "43") (pinfunction "PB7_43") (pintype "unspecified"))
    )
    (net (code "33") (name "/PB8") (class "Default")
      (node (ref "PB") (pin "4") (pinfunction "4_4") (pintype "unspecified"))
      (node (ref "U1") (pin "45") (pinfunction "PB8_45") (pintype "unspecified"))
    )
    (net (code "34") (name "/PB9") (class "Default")
      (node (ref "PB") (pin "3") (pinfunction "3_3") (pintype "unspecified"))
      (node (ref "U1") (pin "46") (pinfunction "PB9_46") (pintype "unspecified"))
    )
    (net (code "35") (name "/PB10") (class "Default")
      (node (ref "PA") (pin "16") (pinfunction "16_16") (pintype "unspecified"))
      (node (ref "U1") (pin "21") (pinfunction "PB10_21") (pintype "unspecified"))
    )
    (net (code "36") (name "/PB11") (class "Default")
      (node (ref "PA") (pin "17") (pinfunction "17_17") (pintype "unspecified"))
      (node (ref "U1") (pin "22") (pinfunction "PB11_22") (pintype "unspecified"))
    )
    (net (code "37") (name "/PB12") (class "Default")
      (node (ref "PB") (pin "17") (pinfunction "17_17") (pintype "unspecified"))
      (node (ref "U1") (pin "25") (pinfunction "PB12_25") (pintype "unspecified"))
    )
    (net (code "38") (name "/PB13") (class "Default")
      (node (ref "PB") (pin "16") (pinfunction "16_16") (pintype "unspecified"))
      (node (ref "U1") (pin "26") (pinfunction "PB13_26") (pintype "unspecified"))
    )
    (net (code "39") (name "/PB14") (class "Default")
      (node (ref "PB") (pin "15") (pinfunction "15_15") (pintype "unspecified"))
      (node (ref "U1") (pin "27") (pinfunction "PB14_27") (pintype "unspecified"))
    )
    (net (code "40") (name "/PB15") (class "Default")
      (node (ref "PB") (pin "14") (pinfunction "14_14") (pintype "unspecified"))
      (node (ref "U1") (pin "28") (pinfunction "PB15_28") (pintype "unspecified"))
    )
    (net (code "41") (name "/PC13") (class "Default")
      (node (ref "PA") (pin "1") (pinfunction "1_1") (pintype "unspecified"))
      (node (ref "U1") (pin "2") (pinfunction "PC13-TAMPER-RTC_2") (pintype "unspecified"))
    )
    (net (code "42") (name "/PC14_32.768") (class "Default")
      (node (ref "C13") (pin "2") (pinfunction "2_2") (pintype "input"))
      (node (ref "PA") (pin "3") (pinfunction "3_3") (pintype "unspecified"))
      (node (ref "U1") (pin "3") (pinfunction "PC14-OSC32_IN_3") (pintype "unspecified"))
      (node (ref "X3") (pin "1") (pinfunction "OE#_1") (pintype "input"))
    )
    (net (code "43") (name "/PC15_32.768") (class "Default")
      (node (ref "C12") (pin "2") (pinfunction "2_2") (pintype "input"))
      (node (ref "PA") (pin "2") (pinfunction "2_2") (pintype "unspecified"))
      (node (ref "U1") (pin "4") (pinfunction "PC15-OSC32_OUT_4") (pintype "unspecified"))
      (node (ref "X3") (pin "4") (pinfunction "OUT_4") (pintype "input"))
    )
    (net (code "44") (name "/RESET") (class "Default")
      (node (ref "C11") (pin "1") (pinfunction "1_1") (pintype "input"))
      (node (ref "KEY1") (pin "1") (pinfunction "1_1") (pintype "input"))
      (node (ref "R7") (pin "1") (pinfunction "1_1") (pintype "input"))
      (node (ref "U1") (pin "7") (pinfunction "NRST_7") (pintype "unspecified"))
    )
    (net (code "45") (name "/SWCLK") (class "Default")
      (node (ref "R5") (pin "2") (pinfunction "2_2") (pintype "input"))
      (node (ref "SWD") (pin "3") (pinfunction "3_3") (pintype "unspecified"))
      (node (ref "U1") (pin "37") (pinfunction "PA14_37") (pintype "unspecified"))
    )
    (net (code "46") (name "/SWDIO") (class "Default")
      (node (ref "R6") (pin "1") (pinfunction "1_1") (pintype "input"))
      (node (ref "SWD") (pin "2") (pinfunction "2_2") (pintype "unspecified"))
      (node (ref "U1") (pin "34") (pinfunction "PA13_34") (pintype "unspecified"))
    )
    (net (code "47") (name "GND") (class "Default")
      (node (ref "C1") (pin "1") (pinfunction "1_1") (pintype "unspecified"))
      (node (ref "C11") (pin "2") (pinfunction "2_2") (pintype "input"))
      (node (ref "C12") (pin "1") (pinfunction "1_1") (pintype "input"))
      (node (ref "C13") (pin "1") (pinfunction "1_1") (pintype "input"))
      (node (ref "C14") (pin "1") (pinfunction "1_1") (pintype "input"))
      (node (ref "C15") (pin "1") (pinfunction "1_1") (pintype "input"))
      (node (ref "C16") (pin "2") (pinfunction "2_2") (pintype "input"))
      (node (ref "C17") (pin "2") (pinfunction "2_2") (pintype "input"))
      (node (ref "C18") (pin "1") (pinfunction "1_1") (pintype "input"))
      (node (ref "C2") (pin "1") (pinfunction "1_1") (pintype "input"))
      (node (ref "C3") (pin "1") (pinfunction "1_1") (pintype "unspecified"))
      (node (ref "C4") (pin "1") (pinfunction "1_1") (pintype "input"))
      (node (ref "C7") (pin "2") (pinfunction "2_2") (pintype "unspecified"))
      (node (ref "C8") (pin "2") (pinfunction "2_2") (pintype "unspecified"))
      (node (ref "H7") (pin "1") (pinfunction "1_1") (pintype "unspecified"))
      (node (ref "KEY1") (pin "2") (pinfunction "2_2") (pintype "input"))
      (node (ref "PA") (pin "13") (pinfunction "13_13") (pintype "unspecified"))
      (node (ref "PA") (pin "4") (pinfunction "4_4") (pintype "unspecified"))
      (node (ref "PB") (pin "2") (pinfunction "2_2") (pintype "unspecified"))
      (node (ref "R1") (pin "2") (pinfunction "2_2") (pintype "input"))
      (node (ref "R13") (pin "2") (pinfunction "2_2") (pintype "input"))
      (node (ref "R5") (pin "1") (pinfunction "1_1") (pintype "input"))
      (node (ref "SWD") (pin "4") (pinfunction "4_4") (pintype "unspecified"))
      (node (ref "U1") (pin "23") (pinfunction "VSS_1_23") (pintype "unspecified"))
      (node (ref "U1") (pin "35") (pinfunction "VSS_2_35") (pintype "unspecified"))
      (node (ref "U1") (pin "47") (pinfunction "VSS_3_47") (pintype "unspecified"))
      (node (ref "U1") (pin "8") (pinfunction "VSSA_8") (pintype "unspecified"))
      (node (ref "U10") (pin "4") (pinfunction "GND_4") (pintype "unspecified"))
      (node (ref "U13") (pin "2") (pinfunction "2_2") (pintype "unspecified"))
      (node (ref "U14") (pin "2") (pinfunction "2_2") (pintype "unspecified"))
      (node (ref "U18") (pin "2") (pinfunction "2_2") (pintype "unspecified"))
      (node (ref "U19") (pin "1") (pinfunction "1_1") (pintype "unspecified"))
      (node (ref "U2") (pin "2") (pinfunction "VSS_2") (pintype "unspecified"))
      (node (ref "U20") (pin "1") (pinfunction "1_1") (pintype "unspecified"))
      (node (ref "U22") (pin "1") (pinfunction "1_1") (pintype "unspecified"))
      (node (ref "U23") (pin "2") (pinfunction "-_2") (pintype "unspecified"))
      (node (ref "U24") (pin "2") (pinfunction "2_2") (pintype "unspecified"))
      (node (ref "U25") (pin "1") (pinfunction "1_1") (pintype "unspecified"))
      (node (ref "U26") (pin "1") (pinfunction "1_1") (pintype "unspecified"))
      (node (ref "U27") (pin "2") (pinfunction "2_2") (pintype "unspecified"))
      (node (ref "U28") (pin "2") (pinfunction "2_2") (pintype "unspecified"))
      (node (ref "U29") (pin "5") (pinfunction "5_5") (pintype "unspecified"))
      (node (ref "U29") (pin "6") (pinfunction "6_6") (pintype "unspecified"))
      (node (ref "U9") (pin "10") (pinfunction "PGND2_10") (pintype "unspecified"))
      (node (ref "U9") (pin "18") (pinfunction "GND_18") (pintype "unspecified"))
      (node (ref "U9") (pin "3") (pinfunction "PGND1_3") (pintype "unspecified"))
      (node (ref "U9") (pin "4") (pinfunction "PGND1_4") (pintype "unspecified"))
      (node (ref "U9") (pin "9") (pinfunction "PGND2_9") (pintype "unspecified"))
      (node (ref "USB1") (pin "5") (pinfunction "GND_5") (pintype "input"))
      (node (ref "X3") (pin "2") (pinfunction "GND_2") (pintype "input"))
      (node (ref "X3") (pin "3") (pinfunction "GND_3") (pintype "input"))
    )
    (net (code "48") (name "Net-(C17-Pad1)") (class "Default")
      (node (ref "C17") (pin "1") (pinfunction "1_1") (pintype "input"))
      (node (ref "KEY3") (pin "1") (pinfunction "1_1") (pintype "input"))
    )
    (net (code "49") (name "Net-(C18-Pad2)") (class "Default")
      (node (ref "C18") (pin "2") (pinfunction "2_2") (pintype "input"))
      (node (ref "KEY4") (pin "1") (pinfunction "1_1") (pintype "input"))
    )
    (net (code "50") (name "Net-(LED1-C)") (class "Default")
      (node (ref "LED1") (pin "1") (pinfunction "C_1") (pintype "input"))
      (node (ref "R1") (pin "1") (pinfunction "1_1") (pintype "input"))
    )
    (net (code "51") (name "Net-(R3-Pad2)") (class "Default")
      (node (ref "R3") (pin "2") (pinfunction "2_2") (pintype "input"))
      (node (ref "U29") (pin "3") (pinfunction "3_3") (pintype "unspecified"))
    )
    (net (code "52") (name "Net-(R4-Pad1)") (class "Default")
      (node (ref "R4") (pin "1") (pinfunction "1_1") (pintype "input"))
      (node (ref "U29") (pin "4") (pinfunction "4_4") (pintype "unspecified"))
    )
    (net (code "53") (name "Net-(USB1-D+)") (class "Default")
      (node (ref "R9") (pin "1") (pinfunction "1_1") (pintype "input"))
      (node (ref "USB1") (pin "3") (pinfunction "D+_3") (pintype "input"))
    )
    (net (code "54") (name "Net-(USB1-D-)") (class "Default")
      (node (ref "R8") (pin "1") (pinfunction "1_1") (pintype "input"))
      (node (ref "USB1") (pin "2") (pinfunction "D-_2") (pintype "input"))
    )
    (net (code "55") (name "VCC3V3") (class "Default")
      (node (ref "C14") (pin "2") (pinfunction "2_2") (pintype "input"))
      (node (ref "C3") (pin "2") (pinfunction "2_2") (pintype "unspecified"))
      (node (ref "C4") (pin "2") (pinfunction "2_2") (pintype "input"))
      (node (ref "H7") (pin "2") (pinfunction "2_2") (pintype "unspecified"))
      (node (ref "KEY2") (pin "1") (pinfunction "1_1") (pintype "input"))
      (node (ref "LED1") (pin "2") (pinfunction "A_2") (pintype "input"))
      (node (ref "PA") (pin "5") (pinfunction "5_5") (pintype "unspecified"))
      (node (ref "PB") (pin "1") (pinfunction "1_1") (pintype "unspecified"))
      (node (ref "R10") (pin "1") (pinfunction "1_1") (pintype "input"))
      (node (ref "R14") (pin "2") (pinfunction "2_2") (pintype "input"))
      (node (ref "R6") (pin "2") (pinfunction "2_2") (pintype "input"))
      (node (ref "R7") (pin "2") (pinfunction "2_2") (pintype "input"))
      (node (ref "SWD") (pin "1") (pinfunction "1_1") (pintype "unspecified"))
      (node (ref "U1") (pin "24") (pinfunction "VDD_1_24") (pintype "unspecified"))
      (node (ref "U1") (pin "36") (pinfunction "VDD_2_36") (pintype "unspecified"))
      (node (ref "U1") (pin "48") (pinfunction "VDD_3_48") (pintype "unspecified"))
      (node (ref "U1") (pin "9") (pinfunction "VDDA_9") (pintype "unspecified"))
      (node (ref "U10") (pin "1") (pinfunction "VDD_1") (pintype "unspecified"))
      (node (ref "U14") (pin "1") (pinfunction "1_1") (pintype "unspecified"))
      (node (ref "U18") (pin "1") (pinfunction "1_1") (pintype "unspecified"))
      (node (ref "U19") (pin "2") (pinfunction "2_2") (pintype "unspecified"))
      (node (ref "U2") (pin "5") (pinfunction "VOUT_5") (pintype "unspecified"))
      (node (ref "U20") (pin "2") (pinfunction "2_2") (pintype "unspecified"))
      (node (ref "U25") (pin "2") (pinfunction "2_2") (pintype "unspecified"))
      (node (ref "U26") (pin "2") (pinfunction "2_2") (pintype "unspecified"))
      (node (ref "U27") (pin "1") (pinfunction "1_1") (pintype "unspecified"))
      (node (ref "U28") (pin "1") (pinfunction "1_1") (pintype "unspecified"))
      (node (ref "U29") (pin "1") (pinfunction "1_1") (pintype "unspecified"))
      (node (ref "U29") (pin "2") (pinfunction "2_2") (pintype "unspecified"))
      (node (ref "U9") (pin "20") (pinfunction "VCC_20") (pintype "unspecified"))
    )
    (net (code "56") (name "VCC_BAT") (class "Default")
      (node (ref "U1") (pin "1") (pinfunction "VBAT_1") (pintype "unspecified"))
      (node (ref "U13") (pin "1") (pinfunction "1_1") (pintype "unspecified"))
      (node (ref "U23") (pin "1") (pinfunction "+_1") (pintype "unspecified"))
      (node (ref "U24") (pin "1") (pinfunction "1_1") (pintype "unspecified"))
    )
    (net (code "57") (name "unconnected-(U2-NC-Pad4)") (class "Default")
      (node (ref "U2") (pin "4") (pinfunction "NC_4") (pintype "unspecified+no_connect"))
    )
    (net (code "58") (name "unconnected-(U10-NC-Pad3)") (class "Default")
      (node (ref "U10") (pin "3") (pinfunction "NC_3") (pintype "unspecified+no_connect"))
    )
    (net (code "59") (name "unconnected-(USB1-EH-Pad6)") (class "Default")
      (node (ref "USB1") (pin "6") (pinfunction "EH_6") (pintype "input+no_connect"))
    )
    (net (code "60") (name "unconnected-(USB1-ID-Pad4)") (class "Default")
      (node (ref "USB1") (pin "4") (pinfunction "ID_4") (pintype "input+no_connect"))
    )
  )
)
